# Wiper_Control_v2.net
KiCad netlist of a schematic drawn in EAGLE
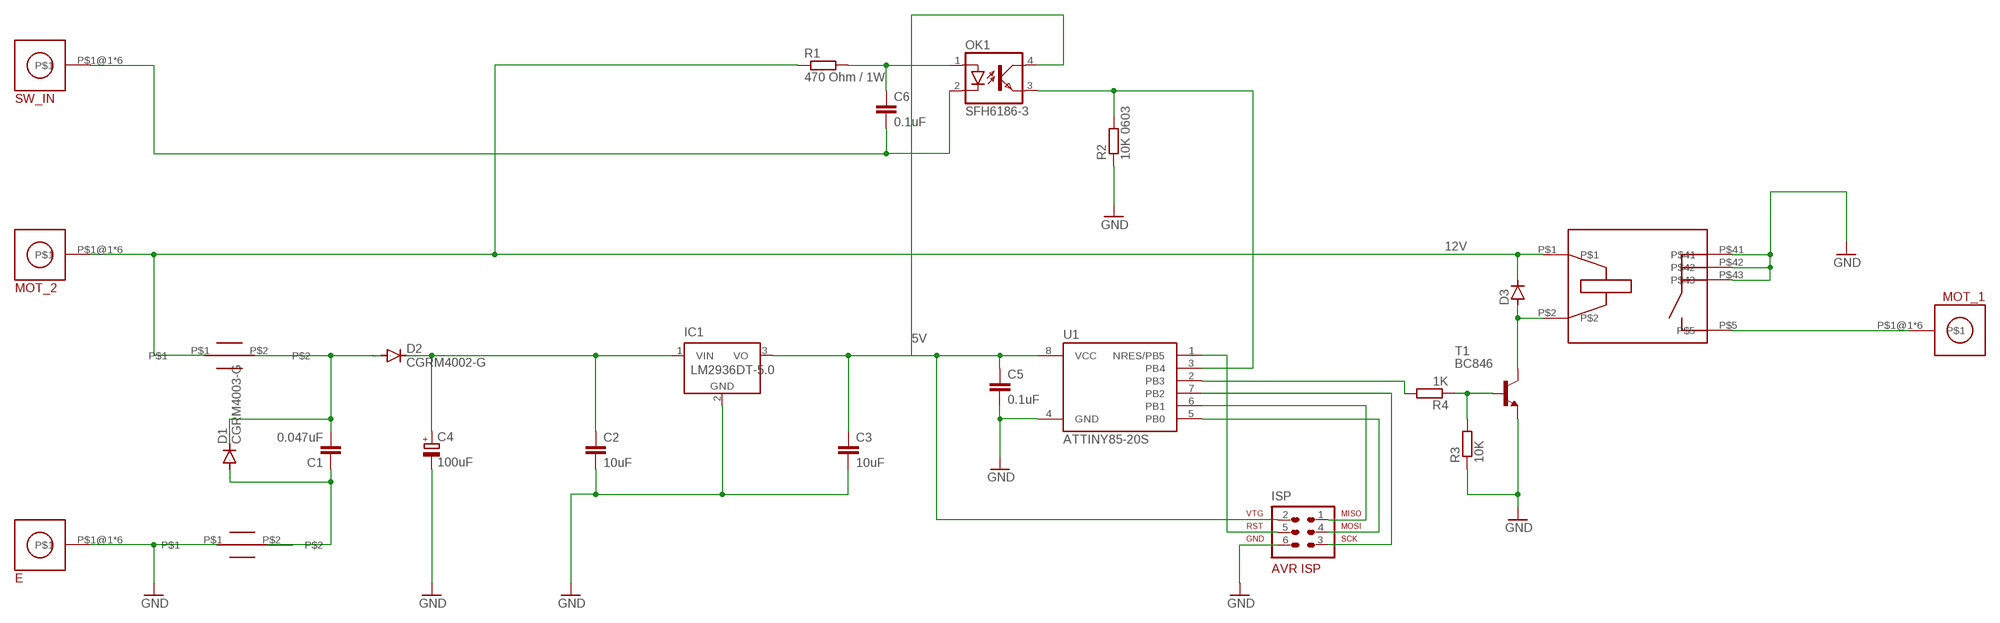
[diagram p0: schematic, sheet 1]

(export (version "E")
  (design (tool "Eeschema 10.0.6"))
  (components
    (comp (ref "B1")
      (value "FBMJ2125")
      (footprint "eagle-import:FBMJ")
      (libsource (lib "eagle-import") (part "FBMJ2125"))
    )
    (comp (ref "B2")
      (value "FBMJ2125")
      (footprint "eagle-import:FBMJ")
      (libsource (lib "eagle-import") (part "FBMJ2125"))
    )
    (comp (ref "C1")
      (value "0.047uF")
      (footprint "eagle-import:C0603")
      (libsource (lib "eagle-import") (part "C-EUC0603"))
    )
    (comp (ref "C2")
      (value "10uF")
      (footprint "eagle-import:C0805")
      (libsource (lib "eagle-import") (part "C-EUC0805"))
    )
    (comp (ref "C3")
      (value "10uF")
      (footprint "eagle-import:C0805")
      (libsource (lib "eagle-import") (part "C-EUC0805"))
    )
    (comp (ref "C4")
      (value "100uF")
      (footprint "eagle-import:E2,5-7")
      (libsource (lib "eagle-import") (part "CPOL-EUE2.5-7"))
    )
    (comp (ref "C5")
      (value "0.1uF")
      (footprint "eagle-import:C0603")
      (libsource (lib "eagle-import") (part "C-EUC0603"))
    )
    (comp (ref "C6")
      (value "0.1uF")
      (footprint "eagle-import:C0603")
      (libsource (lib "eagle-import") (part "C-EUC0603"))
    )
    (comp (ref "D1")
      (value "CGRM4003-G")
      (footprint "eagle-import:SOD-123_MINI-SMA")
      (libsource (lib "eagle-import") (part "CGRM400-G3"))
    )
    (comp (ref "D2")
      (value "CGRM4002-G")
      (footprint "eagle-import:SOD-123_MINI-SMA")
      (libsource (lib "eagle-import") (part "CGRM400-G2"))
    )
    (comp (ref "D3")
      (value "D-SOD123")
      (footprint "eagle-import:SOD123")
      (libsource (lib "eagle-import") (part "D-SOD123"))
    )
    (comp (ref "E")
      (value "M4_SCREW_TERMINAL")
      (footprint "eagle-import:M4_SCREW_TERMINAL")
      (libsource (lib "eagle-import") (part "M4_SCREW_TERMINAL"))
    )
    (comp (ref "IC1")
      (value "LM2936DT-5.0")
      (footprint "eagle-import:TO252")
      (fields (field (name "MF") "NATIONAL SEMICONDUCTOR") (field (name "MPN") "LM2936DT-5.0/NOPB"))
      (libsource (lib "eagle-import") (part "LM2936?DT-5.0"))
    )
    (comp (ref "ISP")
      (value "AVR-ISP-6")
      (footprint "eagle-import:AVR-ISP-6")
      (libsource (lib "eagle-import") (part "AVR-ISP-6"))
    )
    (comp (ref "MOT_1")
      (value "M4_SCREW_TERMINAL")
      (footprint "eagle-import:M4_SCREW_TERMINAL")
      (libsource (lib "eagle-import") (part "M4_SCREW_TERMINAL"))
    )
    (comp (ref "MOT_2")
      (value "M4_SCREW_TERMINAL")
      (footprint "eagle-import:M4_SCREW_TERMINAL")
      (libsource (lib "eagle-import") (part "M4_SCREW_TERMINAL"))
    )
    (comp (ref "OK1")
      (value "SFH6186-3")
      (footprint "eagle-import:SMD4-7")
      (fields (field (name "MF") "VISHAY/TELEFUNKEN"))
      (libsource (lib "eagle-import") (part "SFH618?6-3"))
    )
    (comp (ref "R1")
      (value "470 Ohm / 1W")
      (footprint "eagle-import:R2512")
      (libsource (lib "eagle-import") (part "R-EU_R2512"))
    )
    (comp (ref "R2")
      (value "10K 0603")
      (footprint "eagle-import:R0603")
      (libsource (lib "eagle-import") (part "R-EU_R0603"))
    )
    (comp (ref "R3")
      (value "10K")
      (footprint "eagle-import:R0603")
      (libsource (lib "eagle-import") (part "R-EU_R0603"))
    )
    (comp (ref "R4")
      (value "1K")
      (footprint "eagle-import:R0603")
      (libsource (lib "eagle-import") (part "R-EU_R0603"))
    )
    (comp (ref "SW_IN")
      (value "M4_SCREW_TERMINAL")
      (footprint "eagle-import:M4_SCREW_TERMINAL")
      (libsource (lib "eagle-import") (part "M4_SCREW_TERMINAL"))
    )
    (comp (ref "T1")
      (value "BC846")
      (footprint "eagle-import:SOT23")
      (libsource (lib "eagle-import") (part "BC846"))
    )
    (comp (ref "U$3")
      (value "RELAY")
      (footprint "eagle-import:RELAY")
      (libsource (lib "eagle-import") (part "RELAY"))
    )
    (comp (ref "U1")
      (value "ATTINY85-20S")
      (footprint "eagle-import:SOIC8_EIAJ_208MIL")
      (libsource (lib "eagle-import") (part "ATTINY85S-20"))
    )
  )
  (nets
    (net (code "1") (name "/5V") (class "Default")
      (node (ref "C3") (pin "1") (pinfunction "1_1") (pintype "passive"))
      (node (ref "C5") (pin "1") (pinfunction "1_1") (pintype "passive"))
      (node (ref "IC1") (pin "3") (pinfunction "VO_3") (pintype "passive"))
      (node (ref "ISP") (pin "2") (pinfunction "2_2") (pintype "passive"))
      (node (ref "OK1") (pin "4") (pinfunction "COL_4") (pintype "passive"))
      (node (ref "U1") (pin "8") (pinfunction "VCC_8") (pintype "power_in"))
    )
    (net (code "2") (name "/12V") (class "Default")
      (node (ref "B1") (pin "P$1") (pinfunction "P$1_P$1") (pintype "bidirectional"))
      (node (ref "D3") (pin "1") (pinfunction "C_1") (pintype "passive"))
      (node (ref "MOT_2") (pin "P$1@1") (pinfunction "P$1_P$1@1") (pintype "bidirectional"))
      (node (ref "MOT_2") (pin "P$1@2") (pinfunction "P$1_P$1@2") (pintype "bidirectional"))
      (node (ref "MOT_2") (pin "P$1@3") (pinfunction "P$1_P$1@3") (pintype "bidirectional"))
      (node (ref "MOT_2") (pin "P$1@4") (pinfunction "P$1_P$1@4") (pintype "bidirectional"))
      (node (ref "MOT_2") (pin "P$1@5") (pinfunction "P$1_P$1@5") (pintype "bidirectional"))
      (node (ref "MOT_2") (pin "P$1@6") (pinfunction "P$1_P$1@6") (pintype "bidirectional"))
      (node (ref "R1") (pin "1") (pinfunction "1_1") (pintype "passive"))
      (node (ref "U$3") (pin "P$1") (pinfunction "P$1_P$1") (pintype "bidirectional"))
    )
    (net (code "3") (name "GND") (class "Default")
      (node (ref "B2") (pin "P$1") (pinfunction "P$1_P$1") (pintype "bidirectional"))
      (node (ref "C2") (pin "2") (pinfunction "2_2") (pintype "passive"))
      (node (ref "C3") (pin "2") (pinfunction "2_2") (pintype "passive"))
      (node (ref "C4") (pin "-") (pinfunction "-_-") (pintype "passive"))
      (node (ref "C5") (pin "2") (pinfunction "2_2") (pintype "passive"))
      (node (ref "E") (pin "P$1@1") (pinfunction "P$1_P$1@1") (pintype "bidirectional"))
      (node (ref "E") (pin "P$1@2") (pinfunction "P$1_P$1@2") (pintype "bidirectional"))
      (node (ref "E") (pin "P$1@3") (pinfunction "P$1_P$1@3") (pintype "bidirectional"))
      (node (ref "E") (pin "P$1@4") (pinfunction "P$1_P$1@4") (pintype "bidirectional"))
      (node (ref "E") (pin "P$1@5") (pinfunction "P$1_P$1@5") (pintype "bidirectional"))
      (node (ref "E") (pin "P$1@6") (pinfunction "P$1_P$1@6") (pintype "bidirectional"))
      (node (ref "IC1") (pin "2") (pinfunction "GND_2") (pintype "passive"))
      (node (ref "ISP") (pin "6") (pinfunction "6_6") (pintype "passive"))
      (node (ref "R2") (pin "1") (pinfunction "1_1") (pintype "passive"))
      (node (ref "R3") (pin "1") (pinfunction "1_1") (pintype "passive"))
      (node (ref "T1") (pin "2") (pinfunction "E_2") (pintype "passive"))
      (node (ref "U$3") (pin "P$41") (pinfunction "P$41_P$41") (pintype "bidirectional"))
      (node (ref "U$3") (pin "P$42") (pinfunction "P$42_P$42") (pintype "bidirectional"))
      (node (ref "U$3") (pin "P$43") (pinfunction "P$43_P$43") (pintype "bidirectional"))
      (node (ref "U1") (pin "4") (pinfunction "GND_4") (pintype "power_in"))
    )
    (net (code "4") (name "Net-(B1-PadP$2)") (class "Default")
      (node (ref "B1") (pin "P$2") (pinfunction "P$2_P$2") (pintype "bidirectional"))
      (node (ref "C1") (pin "2") (pinfunction "2_2") (pintype "passive"))
      (node (ref "D1") (pin "C") (pinfunction "C_C") (pintype "passive"))
      (node (ref "D2") (pin "A") (pinfunction "A_A") (pintype "passive"))
    )
    (net (code "5") (name "Net-(B2-PadP$2)") (class "Default")
      (node (ref "B2") (pin "P$2") (pinfunction "P$2_P$2") (pintype "bidirectional"))
      (node (ref "C1") (pin "1") (pinfunction "1_1") (pintype "passive"))
      (node (ref "D1") (pin "A") (pinfunction "A_A") (pintype "passive"))
    )
    (net (code "6") (name "Net-(D3-A)") (class "Default")
      (node (ref "D3") (pin "2") (pinfunction "A_2") (pintype "passive"))
      (node (ref "T1") (pin "3") (pinfunction "C_3") (pintype "passive"))
      (node (ref "U$3") (pin "P$2") (pinfunction "P$2_P$2") (pintype "bidirectional"))
    )
    (net (code "7") (name "Net-(IC1-VIN)") (class "Default")
      (node (ref "C2") (pin "1") (pinfunction "1_1") (pintype "passive"))
      (node (ref "C4") (pin "+") (pinfunction "+_+") (pintype "passive"))
      (node (ref "D2") (pin "C") (pinfunction "C_C") (pintype "passive"))
      (node (ref "IC1") (pin "1") (pinfunction "VIN_1") (pintype "input"))
    )
    (net (code "8") (name "Net-(MOT_1-P$1-PadP$1@1)") (class "Default")
      (node (ref "MOT_1") (pin "P$1@1") (pinfunction "P$1_P$1@1") (pintype "bidirectional"))
      (node (ref "MOT_1") (pin "P$1@2") (pinfunction "P$1_P$1@2") (pintype "bidirectional"))
      (node (ref "MOT_1") (pin "P$1@3") (pinfunction "P$1_P$1@3") (pintype "bidirectional"))
      (node (ref "MOT_1") (pin "P$1@4") (pinfunction "P$1_P$1@4") (pintype "bidirectional"))
      (node (ref "MOT_1") (pin "P$1@5") (pinfunction "P$1_P$1@5") (pintype "bidirectional"))
      (node (ref "MOT_1") (pin "P$1@6") (pinfunction "P$1_P$1@6") (pintype "bidirectional"))
      (node (ref "U$3") (pin "P$5") (pinfunction "P$5_P$5") (pintype "bidirectional"))
    )
    (net (code "9") (name "Net-(OK1-A)") (class "Default")
      (node (ref "C6") (pin "1") (pinfunction "1_1") (pintype "passive"))
      (node (ref "OK1") (pin "1") (pinfunction "A_1") (pintype "passive"))
      (node (ref "R1") (pin "2") (pinfunction "2_2") (pintype "passive"))
    )
    (net (code "10") (name "Net-(OK1-C)") (class "Default")
      (node (ref "C6") (pin "2") (pinfunction "2_2") (pintype "passive"))
      (node (ref "OK1") (pin "2") (pinfunction "C_2") (pintype "passive"))
      (node (ref "SW_IN") (pin "P$1@1") (pinfunction "P$1_P$1@1") (pintype "bidirectional"))
      (node (ref "SW_IN") (pin "P$1@2") (pinfunction "P$1_P$1@2") (pintype "bidirectional"))
      (node (ref "SW_IN") (pin "P$1@3") (pinfunction "P$1_P$1@3") (pintype "bidirectional"))
      (node (ref "SW_IN") (pin "P$1@4") (pinfunction "P$1_P$1@4") (pintype "bidirectional"))
      (node (ref "SW_IN") (pin "P$1@5") (pinfunction "P$1_P$1@5") (pintype "bidirectional"))
      (node (ref "SW_IN") (pin "P$1@6") (pinfunction "P$1_P$1@6") (pintype "bidirectional"))
    )
    (net (code "11") (name "Net-(OK1-EMIT)") (class "Default")
      (node (ref "OK1") (pin "3") (pinfunction "EMIT_3") (pintype "passive"))
      (node (ref "R2") (pin "2") (pinfunction "2_2") (pintype "passive"))
      (node (ref "U1") (pin "3") (pinfunction "PB4_3") (pintype "bidirectional"))
    )
    (net (code "12") (name "Net-(T1-B)") (class "Default")
      (node (ref "R3") (pin "2") (pinfunction "2_2") (pintype "passive"))
      (node (ref "R4") (pin "1") (pinfunction "1_1") (pintype "passive"))
      (node (ref "T1") (pin "1") (pinfunction "B_1") (pintype "passive"))
    )
    (net (code "13") (name "Net-(U1-NRES{slash}PB5)") (class "Default")
      (node (ref "ISP") (pin "5") (pinfunction "5_5") (pintype "passive"))
      (node (ref "U1") (pin "1") (pinfunction "NRES/PB5_1") (pintype "bidirectional"))
    )
    (net (code "14") (name "Net-(U1-PB0)") (class "Default")
      (node (ref "ISP") (pin "4") (pinfunction "4_4") (pintype "passive"))
      (node (ref "U1") (pin "5") (pinfunction "PB0_5") (pintype "bidirectional"))
    )
    (net (code "15") (name "Net-(U1-PB1)") (class "Default")
      (node (ref "ISP") (pin "1") (pinfunction "1_1") (pintype "passive"))
      (node (ref "U1") (pin "6") (pinfunction "PB1_6") (pintype "bidirectional"))
    )
    (net (code "16") (name "Net-(U1-PB2)") (class "Default")
      (node (ref "ISP") (pin "3") (pinfunction "3_3") (pintype "passive"))
      (node (ref "U1") (pin "7") (pinfunction "PB2_7") (pintype "bidirectional"))
    )
    (net (code "17") (name "Net-(U1-PB3)") (class "Default")
      (node (ref "R4") (pin "2") (pinfunction "2_2") (pintype "passive"))
      (node (ref "U1") (pin "2") (pinfunction "PB3_2") (pintype "bidirectional"))
    )
  )
)
